# SensorBoard.net
KiCad netlist of a schematic drawn in Altium Designer
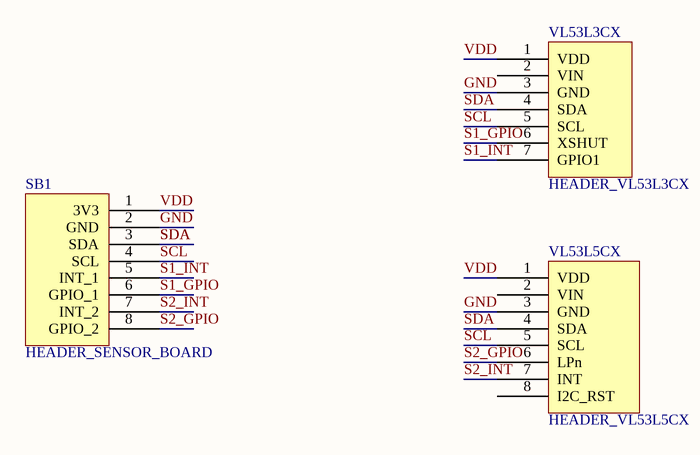
[diagram p0: SensorBoard.SchDoc]

(export (version "E")
  (design (tool "Eeschema 10.0.6"))
  (components
    (comp (ref "SB1")
      (value "HEADER_SENSOR_BOARD")
      (footprint "HEADER_SENSOR_BOARD")
      (description "Sensor Board header")
      (libsource (lib "Components") (part "HEADER_SENSOR_BOARD"))
    )
    (comp (ref "VL53L3CX")
      (value "HEADER_VL53L3CX")
      (footprint "HEADER_VL53L3CX")
      (description "VL53L3CX Time-of-Flight Multi-Target Distance Sensor Carrier with Voltage Regulator, 500cm Max")
      (libsource (lib "Components") (part "HEADER_VL53L3CX"))
    )
    (comp (ref "VL53L5CX")
      (value "HEADER_VL53L5CX")
      (footprint "HEADER_VL53L5CX")
      (description "VL53L5CX Time-of-Flight 8×8-Zone Distance Sensor Carrier with Voltage Regulator, 400cm Max")
      (libsource (lib "Components") (part "HEADER_VL53L5CX"))
    )
  )
  (nets
    (net (code "1") (name "/GND") (class "Default")
      (node (ref "SB1") (pin "2") (pinfunction "GND_2") (pintype "passive"))
      (node (ref "VL53L3CX") (pin "3") (pinfunction "GND_3") (pintype "passive"))
      (node (ref "VL53L5CX") (pin "3") (pinfunction "GND_3") (pintype "passive"))
    )
    (net (code "2") (name "/S1_GPIO") (class "Default")
      (node (ref "SB1") (pin "6") (pinfunction "GPIO_1_6") (pintype "passive"))
      (node (ref "VL53L3CX") (pin "6") (pinfunction "XSHUT_6") (pintype "passive"))
    )
    (net (code "3") (name "/S1_INT") (class "Default")
      (node (ref "SB1") (pin "5") (pinfunction "INT_1_5") (pintype "passive"))
      (node (ref "VL53L3CX") (pin "7") (pinfunction "GPIO1_7") (pintype "passive"))
    )
    (net (code "4") (name "/S2_GPIO") (class "Default")
      (node (ref "SB1") (pin "8") (pinfunction "GPIO_2_8") (pintype "passive"))
      (node (ref "VL53L5CX") (pin "6") (pinfunction "LPn_6") (pintype "passive"))
    )
    (net (code "5") (name "/S2_INT") (class "Default")
      (node (ref "SB1") (pin "7") (pinfunction "INT_2_7") (pintype "passive"))
      (node (ref "VL53L5CX") (pin "7") (pinfunction "INT_7") (pintype "passive"))
    )
    (net (code "6") (name "/SCL") (class "Default")
      (node (ref "SB1") (pin "4") (pinfunction "SCL_4") (pintype "passive"))
      (node (ref "VL53L3CX") (pin "5") (pinfunction "SCL_5") (pintype "passive"))
      (node (ref "VL53L5CX") (pin "5") (pinfunction "SCL_5") (pintype "passive"))
    )
    (net (code "7") (name "/SDA") (class "Default")
      (node (ref "SB1") (pin "3") (pinfunction "SDA_3") (pintype "passive"))
      (node (ref "VL53L3CX") (pin "4") (pinfunction "SDA_4") (pintype "passive"))
      (node (ref "VL53L5CX") (pin "4") (pinfunction "SDA_4") (pintype "passive"))
    )
    (net (code "8") (name "/VDD") (class "Default")
      (node (ref "SB1") (pin "1") (pinfunction "3V3_1") (pintype "passive"))
      (node (ref "VL53L3CX") (pin "1") (pinfunction "VDD_1") (pintype "passive"))
      (node (ref "VL53L5CX") (pin "1") (pinfunction "VDD_1") (pintype "passive"))
    )
    (net (code "9") (name "unconnected-(VL53L3CX-VIN-Pad2)") (class "Default")
      (node (ref "VL53L3CX") (pin "2") (pinfunction "VIN_2") (pintype "passive"))
    )
    (net (code "10") (name "unconnected-(VL53L5CX-I2C_RST-Pad8)") (class "Default")
      (node (ref "VL53L5CX") (pin "8") (pinfunction "I2C_RST_8") (pintype "passive"))
    )
    (net (code "11") (name "unconnected-(VL53L5CX-VIN-Pad2)") (class "Default")
      (node (ref "VL53L5CX") (pin "2") (pinfunction "VIN_2") (pintype "passive"))
    )
  )
)
